# FINAL_DESIGN.net
KiCad netlist of a schematic drawn in EAGLE
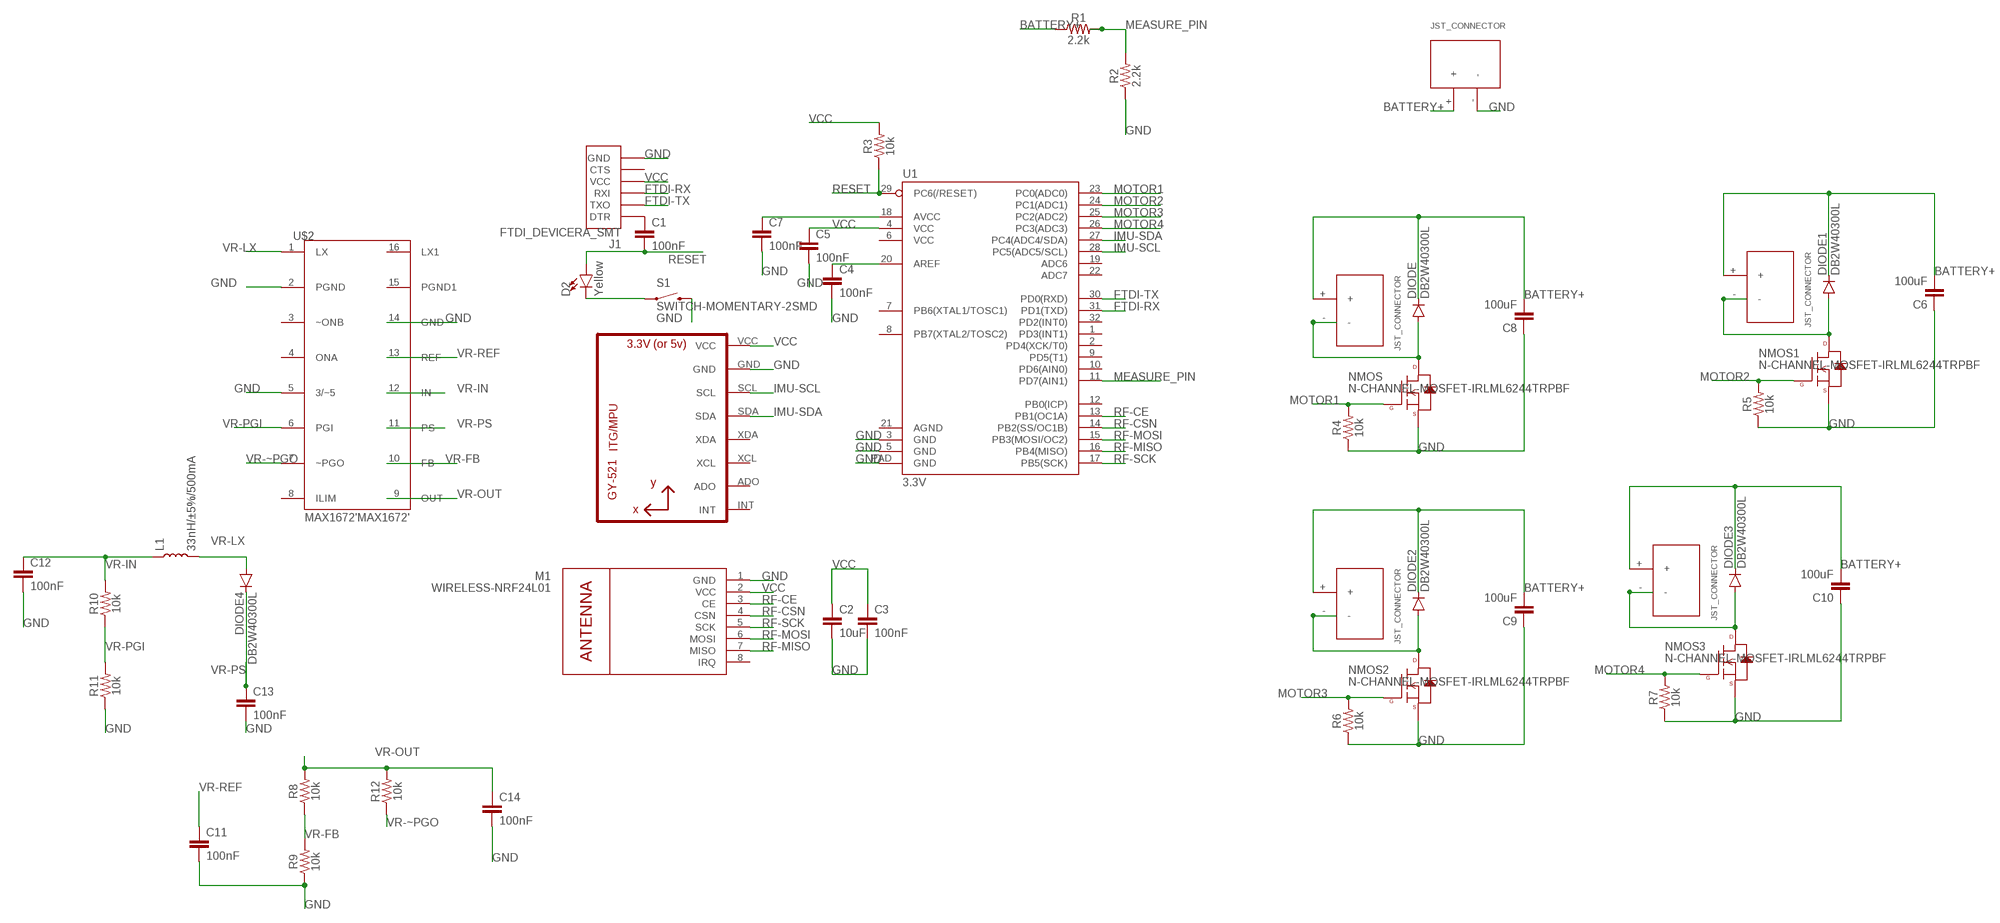
[diagram p0: schematic, sheet 1]

(export (version "E")
  (design (tool "Eeschema 10.0.6"))
  (components
    (comp (ref "C1")
      (value "100nF")
      (footprint "eagle-import:0603-CAP")
      (libsource (lib "eagle-import") (part "0.1UF-25V(+80/-20%)(0603)"))
    )
    (comp (ref "C2")
      (value "10uF")
      (footprint "eagle-import:0603-CAP")
      (libsource (lib "eagle-import") (part "CAP0603-CAP"))
    )
    (comp (ref "C3")
      (value "100nF")
      (footprint "eagle-import:0603-CAP")
      (libsource (lib "eagle-import") (part "CAP0603-CAP"))
    )
    (comp (ref "C4")
      (value "100nF")
      (footprint "eagle-import:0603-CAP")
      (libsource (lib "eagle-import") (part "CAP0603-CAP"))
    )
    (comp (ref "C5")
      (value "100nF")
      (footprint "eagle-import:0603-CAP")
      (libsource (lib "eagle-import") (part "CAP0603-CAP"))
    )
    (comp (ref "C6")
      (value "100uF")
      (footprint "eagle-import:0603-CAP")
      (libsource (lib "eagle-import") (part "CAP0603-CAP"))
    )
    (comp (ref "C7")
      (value "100nF")
      (footprint "eagle-import:0603-CAP")
      (libsource (lib "eagle-import") (part "CAP0603-CAP"))
    )
    (comp (ref "C8")
      (value "100uF")
      (footprint "eagle-import:0603-CAP")
      (libsource (lib "eagle-import") (part "CAP0603-CAP"))
    )
    (comp (ref "C9")
      (value "100uF")
      (footprint "eagle-import:0603-CAP")
      (libsource (lib "eagle-import") (part "CAP0603-CAP"))
    )
    (comp (ref "C10")
      (value "100uF")
      (footprint "eagle-import:0603-CAP")
      (libsource (lib "eagle-import") (part "CAP0603-CAP"))
    )
    (comp (ref "C11")
      (value "100nF")
      (footprint "eagle-import:0603-CAP")
      (libsource (lib "eagle-import") (part "CAP0603-CAP"))
    )
    (comp (ref "C12")
      (value "100nF")
      (footprint "eagle-import:0603-CAP")
      (libsource (lib "eagle-import") (part "CAP0603-CAP"))
    )
    (comp (ref "C13")
      (value "100nF")
      (footprint "eagle-import:0603-CAP")
      (libsource (lib "eagle-import") (part "CAP0603-CAP"))
    )
    (comp (ref "C14")
      (value "100nF")
      (footprint "eagle-import:0603-CAP")
      (libsource (lib "eagle-import") (part "CAP0603-CAP"))
    )
    (comp (ref "D2")
      (value "Yellow")
      (footprint "eagle-import:LED-0603")
      (libsource (lib "eagle-import") (part "LED-YELLOW0603"))
    )
    (comp (ref "DIODE")
      (value "DB2W40300L")
      (footprint "eagle-import:MINI2-F3-B")
      (libsource (lib "eagle-import") (part "DB2W40300L"))
    )
    (comp (ref "DIODE1")
      (value "DB2W40300L")
      (footprint "eagle-import:MINI2-F3-B")
      (libsource (lib "eagle-import") (part "DB2W40300L"))
    )
    (comp (ref "DIODE2")
      (value "DB2W40300L")
      (footprint "eagle-import:MINI2-F3-B")
      (libsource (lib "eagle-import") (part "DB2W40300L"))
    )
    (comp (ref "DIODE3")
      (value "DB2W40300L")
      (footprint "eagle-import:MINI2-F3-B")
      (libsource (lib "eagle-import") (part "DB2W40300L"))
    )
    (comp (ref "DIODE4")
      (value "DB2W40300L")
      (footprint "eagle-import:MINI2-F3-B")
      (libsource (lib "eagle-import") (part "DB2W40300L"))
    )
    (comp (ref "J1")
      (value "FTDI_DEVICERA_SMT")
      (footprint "eagle-import:FTDI_DEVICE_RA_SMT")
      (libsource (lib "eagle-import") (part "FTDI_DEVICERA_SMT"))
    )
    (comp (ref "L1")
      (value "33nH/±5%/500mA")
      (footprint "eagle-import:0603")
      (libsource (lib "eagle-import") (part "INDUCTOR-0603-33NH"))
    )
    (comp (ref "M1")
      (value "WIRELESS-NRF24L01")
      (footprint "eagle-import:WIRELESS-NRF24L01")
      (libsource (lib "eagle-import") (part "WIRELESS-NRF24L01"))
    )
    (comp (ref "MOTOR")
      (value "JST_CONNECTOR_FEMALE")
      (footprint "eagle-import:JST_CONNECTOR_FEMALE")
      (libsource (lib "eagle-import") (part "JST_CONNECTOR_FEMALE"))
    )
    (comp (ref "MOTOR1")
      (value "JST_CONNECTOR_FEMALE")
      (footprint "eagle-import:JST_CONNECTOR_FEMALE")
      (libsource (lib "eagle-import") (part "JST_CONNECTOR_FEMALE"))
    )
    (comp (ref "MOTOR2")
      (value "JST_CONNECTOR_FEMALE")
      (footprint "eagle-import:JST_CONNECTOR_FEMALE")
      (libsource (lib "eagle-import") (part "JST_CONNECTOR_FEMALE"))
    )
    (comp (ref "MOTOR3")
      (value "JST_CONNECTOR_FEMALE")
      (footprint "eagle-import:JST_CONNECTOR_FEMALE")
      (libsource (lib "eagle-import") (part "JST_CONNECTOR_FEMALE"))
    )
    (comp (ref "NMOS")
      (value "N-CHANNEL-MOSFET-IRLML6244TRPBF")
      (footprint "eagle-import:SOT23-3")
      (libsource (lib "eagle-import") (part "N-CHANNEL-MOSFET-IRLML6244TRPBF"))
    )
    (comp (ref "NMOS1")
      (value "N-CHANNEL-MOSFET-IRLML6244TRPBF")
      (footprint "eagle-import:SOT23-3")
      (libsource (lib "eagle-import") (part "N-CHANNEL-MOSFET-IRLML6244TRPBF"))
    )
    (comp (ref "NMOS2")
      (value "N-CHANNEL-MOSFET-IRLML6244TRPBF")
      (footprint "eagle-import:SOT23-3")
      (libsource (lib "eagle-import") (part "N-CHANNEL-MOSFET-IRLML6244TRPBF"))
    )
    (comp (ref "NMOS3")
      (value "N-CHANNEL-MOSFET-IRLML6244TRPBF")
      (footprint "eagle-import:SOT23-3")
      (libsource (lib "eagle-import") (part "N-CHANNEL-MOSFET-IRLML6244TRPBF"))
    )
    (comp (ref "R1")
      (value "2.2k")
      (footprint "eagle-import:0603")
      (libsource (lib "eagle-import") (part "2.2KOHM-0603-1/10W-1%"))
    )
    (comp (ref "R2")
      (value "2.2k")
      (footprint "eagle-import:0603")
      (libsource (lib "eagle-import") (part "2.2KOHM-0603-1/10W-1%"))
    )
    (comp (ref "R3")
      (value "10k")
      (footprint "eagle-import:0603")
      (libsource (lib "eagle-import") (part "2.2KOHM-0603-1/10W-1%"))
    )
    (comp (ref "R4")
      (value "10k")
      (footprint "eagle-import:0603")
      (libsource (lib "eagle-import") (part "2.2KOHM-0603-1/10W-1%"))
    )
    (comp (ref "R5")
      (value "10k")
      (footprint "eagle-import:0603")
      (libsource (lib "eagle-import") (part "2.2KOHM-0603-1/10W-1%"))
    )
    (comp (ref "R6")
      (value "10k")
      (footprint "eagle-import:0603")
      (libsource (lib "eagle-import") (part "2.2KOHM-0603-1/10W-1%"))
    )
    (comp (ref "R7")
      (value "10k")
      (footprint "eagle-import:0603")
      (libsource (lib "eagle-import") (part "2.2KOHM-0603-1/10W-1%"))
    )
    (comp (ref "R8")
      (value "10k")
      (footprint "eagle-import:0603")
      (libsource (lib "eagle-import") (part "2.2KOHM-0603-1/10W-1%"))
    )
    (comp (ref "R9")
      (value "10k")
      (footprint "eagle-import:0603")
      (libsource (lib "eagle-import") (part "2.2KOHM-0603-1/10W-1%"))
    )
    (comp (ref "R10")
      (value "10k")
      (footprint "eagle-import:0603")
      (libsource (lib "eagle-import") (part "2.2KOHM-0603-1/10W-1%"))
    )
    (comp (ref "R11")
      (value "10k")
      (footprint "eagle-import:0603")
      (libsource (lib "eagle-import") (part "2.2KOHM-0603-1/10W-1%"))
    )
    (comp (ref "R12")
      (value "10k")
      (footprint "eagle-import:0603")
      (libsource (lib "eagle-import") (part "2.2KOHM-0603-1/10W-1%"))
    )
    (comp (ref "S1")
      (value "SWITCH-MOMENTARY-2SMD")
      (footprint "eagle-import:TACTILE-SWITCH-SMD")
      (libsource (lib "eagle-import") (part "SWITCH-MOMENTARY-2SMD"))
    )
    (comp (ref "U$1")
      (value "JST_CONNECTOR_FEMALE")
      (footprint "eagle-import:JST_CONNECTOR_FEMALE")
      (libsource (lib "eagle-import") (part "JST_CONNECTOR_FEMALE"))
    )
    (comp (ref "U$2")
      (value "MAX1672'MAX1672'")
      (footprint "eagle-import:21-0055H_16")
      (libsource (lib "eagle-import") (part "MAX1672'MAX1672'"))
    )
    (comp (ref "U1")
      (value "3.3V")
      (footprint "eagle-import:MLF32-PAD")
      (libsource (lib "eagle-import") (part "ATMEGA328P_MLFMLF32"))
    )
    (comp (ref "U2")
      (value "GY-521MPU6050")
      (footprint "eagle-import:GY-521")
      (libsource (lib "eagle-import") (part "GY-521MPU6050"))
    )
  )
  (nets
    (net (code "1") (name "BATTERY+") (class "Default")
      (node (ref "C10") (pin "2") (pinfunction "2_2") (pintype "passive"))
      (node (ref "C6") (pin "2") (pinfunction "2_2") (pintype "passive"))
      (node (ref "C8") (pin "2") (pinfunction "2_2") (pintype "passive"))
      (node (ref "C9") (pin "2") (pinfunction "2_2") (pintype "passive"))
      (node (ref "DIODE") (pin "NEG") (pinfunction "GPIN_NEG") (pintype "passive"))
      (node (ref "DIODE1") (pin "NEG") (pinfunction "GPIN_NEG") (pintype "passive"))
      (node (ref "DIODE2") (pin "NEG") (pinfunction "GPIN_NEG") (pintype "passive"))
      (node (ref "DIODE3") (pin "NEG") (pinfunction "GPIN_NEG") (pintype "passive"))
      (node (ref "MOTOR") (pin "+") (pinfunction "+_+") (pintype "bidirectional"))
      (node (ref "MOTOR1") (pin "+") (pinfunction "+_+") (pintype "bidirectional"))
      (node (ref "MOTOR2") (pin "+") (pinfunction "+_+") (pintype "bidirectional"))
      (node (ref "MOTOR3") (pin "+") (pinfunction "+_+") (pintype "bidirectional"))
      (node (ref "R1") (pin "1") (pinfunction "1_1") (pintype "passive"))
      (node (ref "U$1") (pin "+") (pinfunction "+_+") (pintype "bidirectional"))
    )
    (net (code "2") (name "FTDI-RX") (class "Default")
      (node (ref "J1") (pin "3") (pinfunction "RXI_3") (pintype "bidirectional"))
      (node (ref "U1") (pin "31") (pinfunction "PD1(TXD)_31") (pintype "bidirectional"))
    )
    (net (code "3") (name "FTDI-TX") (class "Default")
      (node (ref "J1") (pin "2") (pinfunction "TXO_2") (pintype "bidirectional"))
      (node (ref "U1") (pin "30") (pinfunction "PD0(RXD)_30") (pintype "bidirectional"))
    )
    (net (code "4") (name "GND") (class "Default")
      (node (ref "C10") (pin "1") (pinfunction "1_1") (pintype "passive"))
      (node (ref "C11") (pin "2") (pinfunction "2_2") (pintype "passive"))
      (node (ref "C12") (pin "2") (pinfunction "2_2") (pintype "passive"))
      (node (ref "C13") (pin "2") (pinfunction "2_2") (pintype "passive"))
      (node (ref "C14") (pin "2") (pinfunction "2_2") (pintype "passive"))
      (node (ref "C2") (pin "2") (pinfunction "2_2") (pintype "passive"))
      (node (ref "C3") (pin "2") (pinfunction "2_2") (pintype "passive"))
      (node (ref "C4") (pin "2") (pinfunction "2_2") (pintype "passive"))
      (node (ref "C5") (pin "2") (pinfunction "2_2") (pintype "passive"))
      (node (ref "C6") (pin "1") (pinfunction "1_1") (pintype "passive"))
      (node (ref "C7") (pin "2") (pinfunction "2_2") (pintype "passive"))
      (node (ref "C8") (pin "1") (pinfunction "1_1") (pintype "passive"))
      (node (ref "C9") (pin "1") (pinfunction "1_1") (pintype "passive"))
      (node (ref "J1") (pin "6") (pinfunction "GND_6") (pintype "bidirectional"))
      (node (ref "M1") (pin "1") (pinfunction "GND_1") (pintype "power_in"))
      (node (ref "NMOS") (pin "2") (pinfunction "S_2") (pintype "passive"))
      (node (ref "NMOS1") (pin "2") (pinfunction "S_2") (pintype "passive"))
      (node (ref "NMOS2") (pin "2") (pinfunction "S_2") (pintype "passive"))
      (node (ref "NMOS3") (pin "2") (pinfunction "S_2") (pintype "passive"))
      (node (ref "R11") (pin "1") (pinfunction "1_1") (pintype "passive"))
      (node (ref "R2") (pin "1") (pinfunction "1_1") (pintype "passive"))
      (node (ref "R4") (pin "1") (pinfunction "1_1") (pintype "passive"))
      (node (ref "R5") (pin "1") (pinfunction "1_1") (pintype "passive"))
      (node (ref "R6") (pin "1") (pinfunction "1_1") (pintype "passive"))
      (node (ref "R7") (pin "1") (pinfunction "1_1") (pintype "passive"))
      (node (ref "R9") (pin "1") (pinfunction "1_1") (pintype "passive"))
      (node (ref "S1") (pin "3") (pinfunction "2_3") (pintype "passive"))
      (node (ref "U$1") (pin "-") (pinfunction "-_-") (pintype "bidirectional"))
      (node (ref "U$2") (pin "14") (pinfunction "GND_14") (pintype "bidirectional"))
      (node (ref "U$2") (pin "2") (pinfunction "PGND_2") (pintype "bidirectional"))
      (node (ref "U$2") (pin "5") (pinfunction "3/~{5}_5") (pintype "bidirectional"))
      (node (ref "U1") (pin "3") (pinfunction "GND_3") (pintype "bidirectional"))
      (node (ref "U1") (pin "5") (pinfunction "GND_5") (pintype "bidirectional"))
      (node (ref "U1") (pin "PAD") (pinfunction "GND_PAD") (pintype "bidirectional"))
      (node (ref "U2") (pin "GND") (pinfunction "GND_GND") (pintype "bidirectional"))
    )
    (net (code "5") (name "IMU-SCL") (class "Default")
      (node (ref "U1") (pin "28") (pinfunction "PC5(ADC5/SCL)_28") (pintype "bidirectional"))
      (node (ref "U2") (pin "SCL") (pinfunction "SCL_SCL") (pintype "bidirectional"))
    )
    (net (code "6") (name "IMU-SDA") (class "Default")
      (node (ref "U1") (pin "27") (pinfunction "PC4(ADC4/SDA)_27") (pintype "bidirectional"))
      (node (ref "U2") (pin "SDA") (pinfunction "SDA_SDA") (pintype "bidirectional"))
    )
    (net (code "7") (name "MEASURE_PIN") (class "Default")
      (node (ref "R1") (pin "2") (pinfunction "2_2") (pintype "passive"))
      (node (ref "R2") (pin "2") (pinfunction "2_2") (pintype "passive"))
      (node (ref "U1") (pin "11") (pinfunction "PD7(AIN1)_11") (pintype "bidirectional"))
    )
    (net (code "8") (name "MOTOR1") (class "Default")
      (node (ref "NMOS") (pin "1") (pinfunction "G_1") (pintype "passive"))
      (node (ref "R4") (pin "2") (pinfunction "2_2") (pintype "passive"))
      (node (ref "U1") (pin "23") (pinfunction "PC0(ADC0)_23") (pintype "bidirectional"))
    )
    (net (code "9") (name "MOTOR2") (class "Default")
      (node (ref "NMOS1") (pin "1") (pinfunction "G_1") (pintype "passive"))
      (node (ref "R5") (pin "2") (pinfunction "2_2") (pintype "passive"))
      (node (ref "U1") (pin "24") (pinfunction "PC1(ADC1)_24") (pintype "bidirectional"))
    )
    (net (code "10") (name "MOTOR3") (class "Default")
      (node (ref "NMOS2") (pin "1") (pinfunction "G_1") (pintype "passive"))
      (node (ref "R6") (pin "2") (pinfunction "2_2") (pintype "passive"))
      (node (ref "U1") (pin "25") (pinfunction "PC2(ADC2)_25") (pintype "bidirectional"))
    )
    (net (code "11") (name "MOTOR4") (class "Default")
      (node (ref "NMOS3") (pin "1") (pinfunction "G_1") (pintype "passive"))
      (node (ref "R7") (pin "2") (pinfunction "2_2") (pintype "passive"))
      (node (ref "U1") (pin "26") (pinfunction "PC3(ADC3)_26") (pintype "bidirectional"))
    )
    (net (code "12") (name "Net-(D2-PadC)") (class "Default")
      (node (ref "D2") (pin "C") (pinfunction "C_C") (pintype "passive"))
      (node (ref "S1") (pin "1") (pinfunction "1_1") (pintype "passive"))
    )
    (net (code "13") (name "Net-(DIODE-PPIN)") (class "Default")
      (node (ref "DIODE") (pin "POS") (pinfunction "PPIN_POS") (pintype "passive"))
      (node (ref "MOTOR") (pin "-") (pinfunction "-_-") (pintype "bidirectional"))
      (node (ref "NMOS") (pin "3") (pinfunction "D_3") (pintype "passive"))
    )
    (net (code "14") (name "Net-(DIODE1-PPIN)") (class "Default")
      (node (ref "DIODE1") (pin "POS") (pinfunction "PPIN_POS") (pintype "passive"))
      (node (ref "MOTOR1") (pin "-") (pinfunction "-_-") (pintype "bidirectional"))
      (node (ref "NMOS1") (pin "3") (pinfunction "D_3") (pintype "passive"))
    )
    (net (code "15") (name "Net-(DIODE2-PPIN)") (class "Default")
      (node (ref "DIODE2") (pin "POS") (pinfunction "PPIN_POS") (pintype "passive"))
      (node (ref "MOTOR2") (pin "-") (pinfunction "-_-") (pintype "bidirectional"))
      (node (ref "NMOS2") (pin "3") (pinfunction "D_3") (pintype "passive"))
    )
    (net (code "16") (name "Net-(DIODE3-PPIN)") (class "Default")
      (node (ref "DIODE3") (pin "POS") (pinfunction "PPIN_POS") (pintype "passive"))
      (node (ref "MOTOR3") (pin "-") (pinfunction "-_-") (pintype "bidirectional"))
      (node (ref "NMOS3") (pin "3") (pinfunction "D_3") (pintype "passive"))
    )
    (net (code "17") (name "Net-(J1-DTR)") (class "Default")
      (node (ref "C1") (pin "1") (pinfunction "1_1") (pintype "passive"))
      (node (ref "J1") (pin "1") (pinfunction "DTR_1") (pintype "bidirectional"))
    )
    (net (code "18") (name "Net-(U1-AREF)") (class "Default")
      (node (ref "C4") (pin "1") (pinfunction "1_1") (pintype "passive"))
      (node (ref "U1") (pin "20") (pinfunction "AREF_20") (pintype "bidirectional"))
    )
    (net (code "19") (name "Net-(U1-AVCC)") (class "Default")
      (node (ref "C7") (pin "1") (pinfunction "1_1") (pintype "passive"))
      (node (ref "U1") (pin "18") (pinfunction "AVCC_18") (pintype "bidirectional"))
    )
    (net (code "20") (name "RESET") (class "Default")
      (node (ref "C1") (pin "2") (pinfunction "2_2") (pintype "passive"))
      (node (ref "D2") (pin "A") (pinfunction "A_A") (pintype "passive"))
      (node (ref "R3") (pin "1") (pinfunction "1_1") (pintype "passive"))
      (node (ref "U1") (pin "29") (pinfunction "PC6(/RESET)_29") (pintype "bidirectional"))
    )
    (net (code "21") (name "RF-CE") (class "Default")
      (node (ref "M1") (pin "3") (pinfunction "CE_3") (pintype "bidirectional"))
      (node (ref "U1") (pin "13") (pinfunction "PB1(OC1A)_13") (pintype "bidirectional"))
    )
    (net (code "22") (name "RF-CSN") (class "Default")
      (node (ref "M1") (pin "4") (pinfunction "CSN_4") (pintype "bidirectional"))
      (node (ref "U1") (pin "14") (pinfunction "PB2(SS/OC1B)_14") (pintype "bidirectional"))
    )
    (net (code "23") (name "RF-MISO") (class "Default")
      (node (ref "M1") (pin "7") (pinfunction "MISO_7") (pintype "bidirectional"))
      (node (ref "U1") (pin "16") (pinfunction "PB4(MISO)_16") (pintype "bidirectional"))
    )
    (net (code "24") (name "RF-MOSI") (class "Default")
      (node (ref "M1") (pin "6") (pinfunction "MOSI_6") (pintype "bidirectional"))
      (node (ref "U1") (pin "15") (pinfunction "PB3(MOSI/OC2)_15") (pintype "bidirectional"))
    )
    (net (code "25") (name "RF-SCK") (class "Default")
      (node (ref "M1") (pin "5") (pinfunction "SCK_5") (pintype "bidirectional"))
      (node (ref "U1") (pin "17") (pinfunction "PB5(SCK)_17") (pintype "bidirectional"))
    )
    (net (code "26") (name "VCC") (class "Default")
      (node (ref "C2") (pin "1") (pinfunction "1_1") (pintype "passive"))
      (node (ref "C3") (pin "1") (pinfunction "1_1") (pintype "passive"))
      (node (ref "C5") (pin "1") (pinfunction "1_1") (pintype "passive"))
      (node (ref "J1") (pin "4") (pinfunction "VCC_4") (pintype "bidirectional"))
      (node (ref "M1") (pin "2") (pinfunction "VCC_2") (pintype "power_in"))
      (node (ref "R3") (pin "2") (pinfunction "2_2") (pintype "passive"))
      (node (ref "U1") (pin "4") (pinfunction "VCC_4") (pintype "bidirectional"))
      (node (ref "U2") (pin "VCC") (pinfunction "VCC_VCC") (pintype "bidirectional"))
    )
    (net (code "27") (name "VR-FB") (class "Default")
      (node (ref "R8") (pin "1") (pinfunction "1_1") (pintype "passive"))
      (node (ref "R9") (pin "2") (pinfunction "2_2") (pintype "passive"))
      (node (ref "U$2") (pin "10") (pinfunction "FB_10") (pintype "bidirectional"))
    )
    (net (code "28") (name "VR-IN") (class "Default")
      (node (ref "C12") (pin "1") (pinfunction "1_1") (pintype "passive"))
      (node (ref "L1") (pin "1") (pinfunction "1_1") (pintype "passive"))
      (node (ref "R10") (pin "2") (pinfunction "2_2") (pintype "passive"))
      (node (ref "U$2") (pin "12") (pinfunction "IN_12") (pintype "bidirectional"))
    )
    (net (code "29") (name "VR-LX") (class "Default")
      (node (ref "DIODE4") (pin "POS") (pinfunction "PPIN_POS") (pintype "passive"))
      (node (ref "L1") (pin "2") (pinfunction "2_2") (pintype "passive"))
      (node (ref "U$2") (pin "1") (pinfunction "LX_1") (pintype "bidirectional"))
    )
    (net (code "30") (name "VR-OUT") (class "Default")
      (node (ref "C14") (pin "1") (pinfunction "1_1") (pintype "passive"))
      (node (ref "R12") (pin "2") (pinfunction "2_2") (pintype "passive"))
      (node (ref "R8") (pin "2") (pinfunction "2_2") (pintype "passive"))
      (node (ref "U$2") (pin "9") (pinfunction "OUT_9") (pintype "bidirectional"))
    )
    (net (code "31") (name "VR-PGI") (class "Default")
      (node (ref "R10") (pin "1") (pinfunction "1_1") (pintype "passive"))
      (node (ref "R11") (pin "2") (pinfunction "2_2") (pintype "passive"))
      (node (ref "U$2") (pin "6") (pinfunction "PGI_6") (pintype "bidirectional"))
    )
    (net (code "32") (name "VR-PS") (class "Default")
      (node (ref "C13") (pin "1") (pinfunction "1_1") (pintype "passive"))
      (node (ref "DIODE4") (pin "NEG") (pinfunction "GPIN_NEG") (pintype "passive"))
      (node (ref "U$2") (pin "11") (pinfunction "PS_11") (pintype "bidirectional"))
    )
    (net (code "33") (name "VR-REF") (class "Default")
      (node (ref "C11") (pin "1") (pinfunction "1_1") (pintype "passive"))
      (node (ref "U$2") (pin "13") (pinfunction "REF_13") (pintype "bidirectional"))
    )
    (net (code "34") (name "VR-~{PGO}") (class "Default")
      (node (ref "R12") (pin "1") (pinfunction "1_1") (pintype "passive"))
      (node (ref "U$2") (pin "7") (pinfunction "~{PGO}_7") (pintype "bidirectional"))
    )
    (net (code "35") (name "unconnected-(J1-CTS-Pad5)") (class "Default")
      (node (ref "J1") (pin "5") (pinfunction "CTS_5") (pintype "bidirectional"))
    )
    (net (code "36") (name "unconnected-(M1-IRQ-Pad8)") (class "Default")
      (node (ref "M1") (pin "8") (pinfunction "IRQ_8") (pintype "bidirectional"))
    )
    (net (code "37") (name "unconnected-(U$2-ILIM-Pad8)") (class "Default")
      (node (ref "U$2") (pin "8") (pinfunction "ILIM_8") (pintype "bidirectional"))
    )
    (net (code "38") (name "unconnected-(U$2-LX1-Pad16)") (class "Default")
      (node (ref "U$2") (pin "16") (pinfunction "LX1_16") (pintype "bidirectional"))
    )
    (net (code "39") (name "unconnected-(U$2-ONA-Pad4)") (class "Default")
      (node (ref "U$2") (pin "4") (pinfunction "ONA_4") (pintype "bidirectional"))
    )
    (net (code "40") (name "unconnected-(U$2-PGND1-Pad15)") (class "Default")
      (node (ref "U$2") (pin "15") (pinfunction "PGND1_15") (pintype "bidirectional"))
    )
    (net (code "41") (name "unconnected-(U$2-~{ONB}-Pad3)") (class "Default")
      (node (ref "U$2") (pin "3") (pinfunction "~{ONB}_3") (pintype "bidirectional"))
    )
    (net (code "42") (name "unconnected-(U1-ADC6-Pad19)") (class "Default")
      (node (ref "U1") (pin "19") (pinfunction "ADC6_19") (pintype "bidirectional"))
    )
    (net (code "43") (name "unconnected-(U1-ADC7-Pad22)") (class "Default")
      (node (ref "U1") (pin "22") (pinfunction "ADC7_22") (pintype "bidirectional"))
    )
    (net (code "44") (name "unconnected-(U1-AGND-Pad21)") (class "Default")
      (node (ref "U1") (pin "21") (pinfunction "AGND_21") (pintype "bidirectional"))
    )
    (net (code "45") (name "unconnected-(U1-PB0(ICP)-Pad12)") (class "Default")
      (node (ref "U1") (pin "12") (pinfunction "PB0(ICP)_12") (pintype "bidirectional"))
    )
    (net (code "46") (name "unconnected-(U1-PB6(XTAL1{slash}TOSC1)-Pad7)") (class "Default")
      (node (ref "U1") (pin "7") (pinfunction "PB6(XTAL1/TOSC1)_7") (pintype "bidirectional"))
    )
    (net (code "47") (name "unconnected-(U1-PB7(XTAL2{slash}TOSC2)-Pad8)") (class "Default")
      (node (ref "U1") (pin "8") (pinfunction "PB7(XTAL2/TOSC2)_8") (pintype "bidirectional"))
    )
    (net (code "48") (name "unconnected-(U1-PD2(INT0)-Pad32)") (class "Default")
      (node (ref "U1") (pin "32") (pinfunction "PD2(INT0)_32") (pintype "bidirectional"))
    )
    (net (code "49") (name "unconnected-(U1-PD3(INT1)-Pad1)") (class "Default")
      (node (ref "U1") (pin "1") (pinfunction "PD3(INT1)_1") (pintype "bidirectional"))
    )
    (net (code "50") (name "unconnected-(U1-PD4(XCK{slash}T0)-Pad2)") (class "Default")
      (node (ref "U1") (pin "2") (pinfunction "PD4(XCK/T0)_2") (pintype "bidirectional"))
    )
    (net (code "51") (name "unconnected-(U1-PD5(T1)-Pad9)") (class "Default")
      (node (ref "U1") (pin "9") (pinfunction "PD5(T1)_9") (pintype "bidirectional"))
    )
    (net (code "52") (name "unconnected-(U1-PD6(AIN0)-Pad10)") (class "Default")
      (node (ref "U1") (pin "10") (pinfunction "PD6(AIN0)_10") (pintype "bidirectional"))
    )
    (net (code "53") (name "unconnected-(U1-VCC-Pad6)") (class "Default")
      (node (ref "U1") (pin "6") (pinfunction "VCC_6") (pintype "bidirectional"))
    )
    (net (code "54") (name "unconnected-(U2-PadADO)") (class "Default")
      (node (ref "U2") (pin "ADO") (pinfunction "ADO_ADO") (pintype "bidirectional"))
    )
    (net (code "55") (name "unconnected-(U2-PadINT)") (class "Default")
      (node (ref "U2") (pin "INT") (pinfunction "INT_INT") (pintype "bidirectional"))
    )
    (net (code "56") (name "unconnected-(U2-PadXCL)") (class "Default")
      (node (ref "U2") (pin "XCL") (pinfunction "XCL_XCL") (pintype "bidirectional"))
    )
    (net (code "57") (name "unconnected-(U2-PadXDA)") (class "Default")
      (node (ref "U2") (pin "XDA") (pinfunction "XDA_XDA") (pintype "bidirectional"))
    )
  )
)
